# PCIE_CLK.net
KiCad netlist of a schematic drawn in Altium Designer
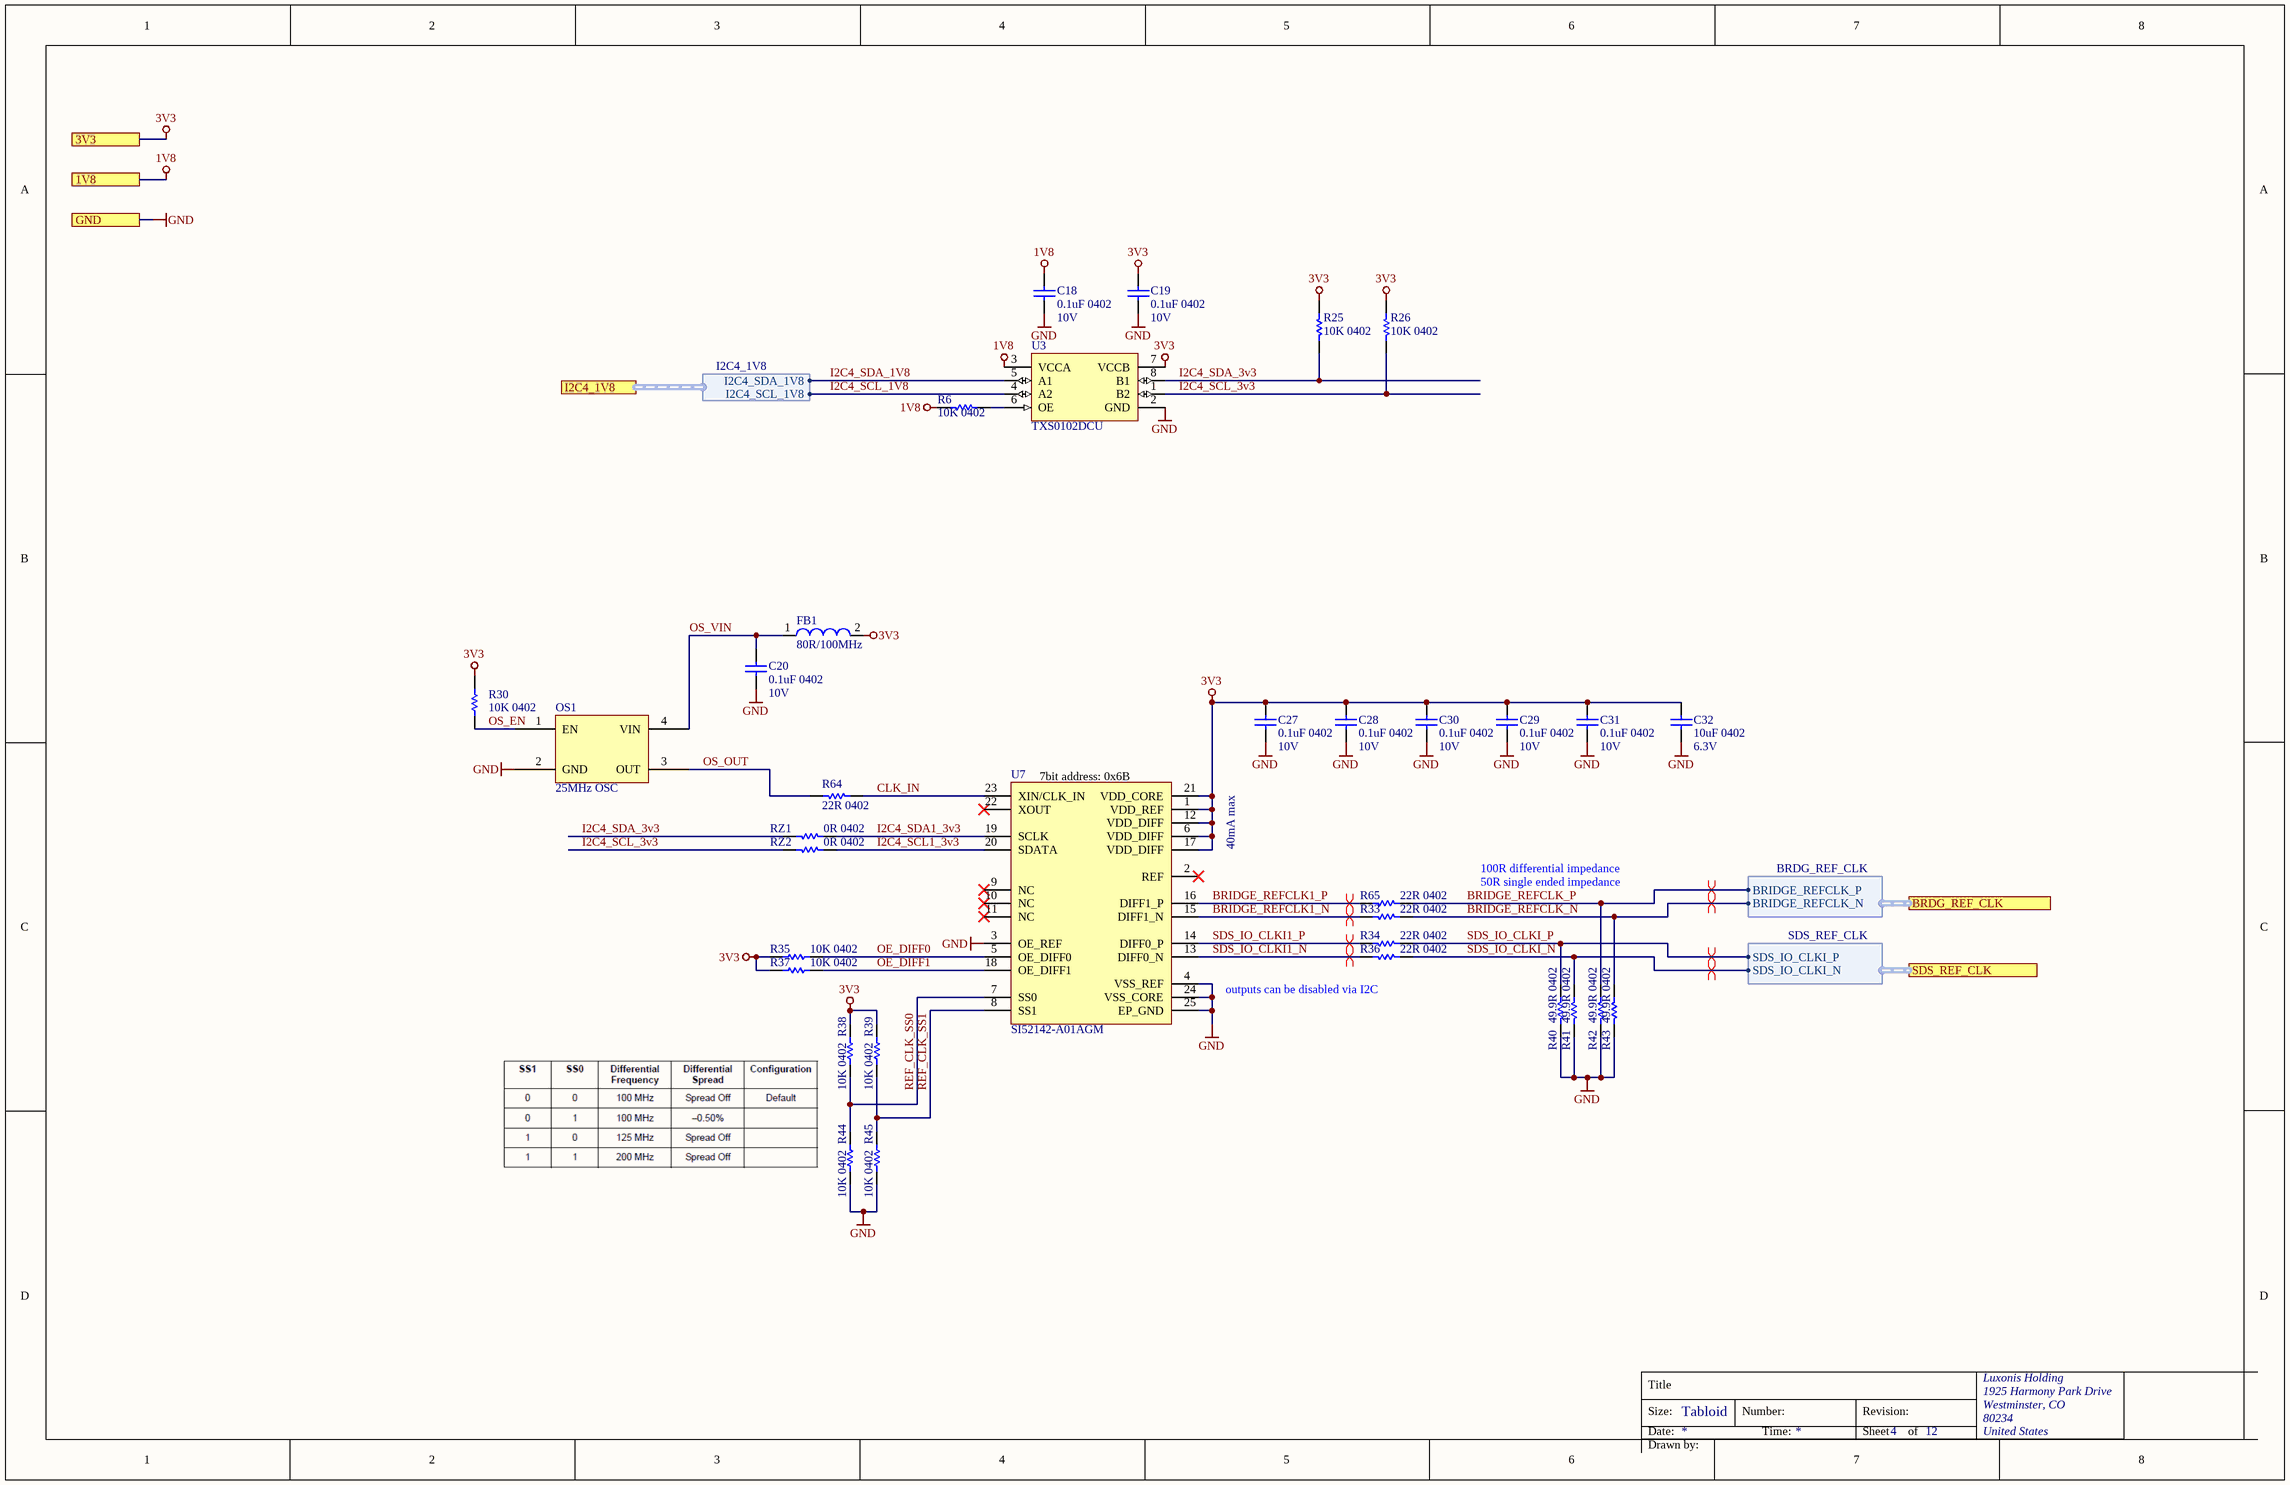
[diagram p0: PCIE_CLK.SchDoc]

(export (version "E")
  (design (tool "Eeschema 10.0.6"))
  (components
    (comp (ref "C18")
      (value "0.1uF 0402")
      (footprint "CAP_Altium_Vault_Generic:CAPC0402(1005)70_N")
      (description "CAP CER 0.1UF 10V X7R 0402 5%")
      (fields (field (name "TOLERANCE") "5%") (field (name "VOLTAGE RATING") "10V"))
      (libsource (lib "LuxonisMaster") (part "GRM155R71A104JA01D"))
    )
    (comp (ref "C19")
      (value "0.1uF 0402")
      (footprint "CAP_Altium_Vault_Generic:CAPC0402(1005)70_N")
      (description "CAP CER 0.1UF 10V X7R 0402 5%")
      (fields (field (name "TOLERANCE") "5%") (field (name "VOLTAGE RATING") "10V"))
      (libsource (lib "LuxonisMaster") (part "GRM155R71A104JA01D"))
    )
    (comp (ref "C20")
      (value "0.1uF 0402")
      (footprint "CAP_Altium_Vault_Generic:CAPC0402(1005)70_N")
      (description "CAP CER 0.1UF 10V X7R 0402 5%")
      (fields (field (name "TOLERANCE") "5%") (field (name "VOLTAGE RATING") "10V"))
      (libsource (lib "LuxonisMaster") (part "GRM155R71A104JA01D"))
    )
    (comp (ref "C27")
      (value "0.1uF 0402")
      (footprint "CAP_Altium_Vault_Generic:CAPC0402(1005)70_N")
      (description "CAP CER 0.1UF 10V X7R 0402 5%")
      (fields (field (name "TOLERANCE") "5%") (field (name "VOLTAGE RATING") "10V"))
      (libsource (lib "LuxonisMaster") (part "GRM155R71A104JA01D"))
    )
    (comp (ref "C28")
      (value "0.1uF 0402")
      (footprint "CAP_Altium_Vault_Generic:CAPC0402(1005)70_N")
      (description "CAP CER 0.1UF 10V X7R 0402 5%")
      (fields (field (name "TOLERANCE") "5%") (field (name "VOLTAGE RATING") "10V"))
      (libsource (lib "LuxonisMaster") (part "GRM155R71A104JA01D"))
    )
    (comp (ref "C29")
      (value "0.1uF 0402")
      (footprint "CAP_Altium_Vault_Generic:CAPC0402(1005)70_N")
      (description "CAP CER 0.1UF 10V X7R 0402 5%")
      (fields (field (name "TOLERANCE") "5%") (field (name "VOLTAGE RATING") "10V"))
      (libsource (lib "LuxonisMaster") (part "GRM155R71A104JA01D"))
    )
    (comp (ref "C30")
      (value "0.1uF 0402")
      (footprint "CAP_Altium_Vault_Generic:CAPC0402(1005)70_N")
      (description "CAP CER 0.1UF 10V X7R 0402 5%")
      (fields (field (name "TOLERANCE") "5%") (field (name "VOLTAGE RATING") "10V"))
      (libsource (lib "LuxonisMaster") (part "GRM155R71A104JA01D"))
    )
    (comp (ref "C31")
      (value "0.1uF 0402")
      (footprint "CAP_Altium_Vault_Generic:CAPC0402(1005)70_N")
      (description "CAP CER 0.1UF 10V X7R 0402 5%")
      (fields (field (name "TOLERANCE") "5%") (field (name "VOLTAGE RATING") "10V"))
      (libsource (lib "LuxonisMaster") (part "GRM155R71A104JA01D"))
    )
    (comp (ref "C32")
      (value "10uF 0402")
      (footprint "CAP_Altium_Vault_Generic:CAPC0402(1005)70_N")
      (description "CAP CER 10UF 6.3V X5R 0402 20%")
      (fields (field (name "TOLERANCE") "20%") (field (name "VOLTAGE RATING") "6.3V"))
      (libsource (lib "LuxonisMaster") (part "GRM155R60J106ME15D"))
    )
    (comp (ref "FB1")
      (value "80R/100MHz")
      (footprint "LuxonisMaster:BK1608HS800-T_N")
      (description "FERRITE BEAD 80 OHM 0603 1LN")
      (fields (field (name "TOLERANCE") "25%"))
      (libsource (lib "LuxonisMaster") (part "BK1608HS800-T"))
    )
    (comp (ref "OS1")
      (value "25MHz OSC")
      (footprint "BW2098POE:ASDMB-25.000MHZ-LC-T")
      (description "MEMS OSC XO 25.0000MHZ LVCMOS")
      (libsource (lib "BW2098POE") (part "ASDMB-25.000MHZ-LC-T"))
    )
    (comp (ref "R6")
      (value "10K 0402")
      (footprint "RES_Altium_Vault_Generic:RESC0402(1005)_N")
      (fields (field (name "TOLERANCE") "1%"))
      (libsource (lib "LuxonisMaster") (part "RC0402FR-1310KL"))
    )
    (comp (ref "R25")
      (value "10K 0402")
      (footprint "RES_Altium_Vault_Generic:RESC0402(1005)_N")
      (fields (field (name "TOLERANCE") "1%"))
      (libsource (lib "LuxonisMaster") (part "RC0402FR-1310KL"))
    )
    (comp (ref "R26")
      (value "10K 0402")
      (footprint "RES_Altium_Vault_Generic:RESC0402(1005)_N")
      (fields (field (name "TOLERANCE") "1%"))
      (libsource (lib "LuxonisMaster") (part "RC0402FR-1310KL"))
    )
    (comp (ref "R30")
      (value "10K 0402")
      (footprint "RES_Altium_Vault_Generic:RESC0402(1005)_N")
      (fields (field (name "TOLERANCE") "1%"))
      (libsource (lib "LuxonisMaster") (part "RC0402FR-1310KL"))
    )
    (comp (ref "R33")
      (value "22R 0402")
      (footprint "RES_Altium_Vault_Generic:RESC0402(1005)_L")
      (description "RES SMD 22 OHM 1% 1/16W 0402")
      (fields (field (name "TOLERANCE") "1%"))
      (libsource (lib "BW2098POE") (part "RC0402FR-0722RL"))
    )
    (comp (ref "R34")
      (value "22R 0402")
      (footprint "RES_Altium_Vault_Generic:RESC0402(1005)_L")
      (description "RES SMD 22 OHM 1% 1/16W 0402")
      (fields (field (name "TOLERANCE") "1%"))
      (libsource (lib "BW2098POE") (part "RC0402FR-0722RL"))
    )
    (comp (ref "R35")
      (value "10K 0402")
      (footprint "RES_Altium_Vault_Generic:RESC0402(1005)_N")
      (fields (field (name "TOLERANCE") "1%"))
      (libsource (lib "LuxonisMaster") (part "RC0402FR-1310KL"))
    )
    (comp (ref "R36")
      (value "22R 0402")
      (footprint "RES_Altium_Vault_Generic:RESC0402(1005)_L")
      (description "RES SMD 22 OHM 1% 1/16W 0402")
      (fields (field (name "TOLERANCE") "1%"))
      (libsource (lib "BW2098POE") (part "RC0402FR-0722RL"))
    )
    (comp (ref "R37")
      (value "10K 0402")
      (footprint "RES_Altium_Vault_Generic:RESC0402(1005)_N")
      (fields (field (name "TOLERANCE") "1%"))
      (libsource (lib "LuxonisMaster") (part "RC0402FR-1310KL"))
    )
    (comp (ref "R38")
      (value "10K 0402")
      (footprint "RES_Altium_Vault_Generic:RESC0402(1005)_N")
      (fields (field (name "TOLERANCE") "1%"))
      (libsource (lib "LuxonisMaster") (part "RC0402FR-1310KL"))
    )
    (comp (ref "R39")
      (value "10K 0402")
      (footprint "RES_Altium_Vault_Generic:RESC0402(1005)_N")
      (fields (field (name "TOLERANCE") "1%"))
      (libsource (lib "LuxonisMaster") (part "RC0402FR-1310KL"))
    )
    (comp (ref "R40")
      (value "49.9R 0402")
      (footprint "RES_Altium_Vault_Generic:RESC0402(1005)_L")
      (description "RES SMD 49.9 OHM 1% 1/16W 0402")
      (fields (field (name "TOLERANCE") "1%"))
      (libsource (lib "LuxonisMaster") (part "RC0402FR-0749R9L"))
    )
    (comp (ref "R41")
      (value "49.9R 0402")
      (footprint "RES_Altium_Vault_Generic:RESC0402(1005)_L")
      (description "RES SMD 49.9 OHM 1% 1/16W 0402")
      (fields (field (name "TOLERANCE") "1%"))
      (libsource (lib "LuxonisMaster") (part "RC0402FR-0749R9L"))
    )
    (comp (ref "R42")
      (value "49.9R 0402")
      (footprint "RES_Altium_Vault_Generic:RESC0402(1005)_L")
      (description "RES SMD 49.9 OHM 1% 1/16W 0402")
      (fields (field (name "TOLERANCE") "1%"))
      (libsource (lib "LuxonisMaster") (part "RC0402FR-0749R9L"))
    )
    (comp (ref "R43")
      (value "49.9R 0402")
      (footprint "RES_Altium_Vault_Generic:RESC0402(1005)_L")
      (description "RES SMD 49.9 OHM 1% 1/16W 0402")
      (fields (field (name "TOLERANCE") "1%"))
      (libsource (lib "LuxonisMaster") (part "RC0402FR-0749R9L"))
    )
    (comp (ref "R44")
      (value "10K 0402")
      (footprint "RES_Altium_Vault_Generic:RESC0402(1005)_N")
      (fields (field (name "TOLERANCE") "1%"))
      (libsource (lib "LuxonisMaster") (part "RC0402FR-1310KL"))
    )
    (comp (ref "R45")
      (value "10K 0402")
      (footprint "RES_Altium_Vault_Generic:RESC0402(1005)_N")
      (fields (field (name "TOLERANCE") "1%"))
      (libsource (lib "LuxonisMaster") (part "RC0402FR-1310KL"))
    )
    (comp (ref "R64")
      (value "22R 0402")
      (footprint "RES_Altium_Vault_Generic:RESC0402(1005)_N")
      (description "RES SMD 22 OHM 1% 1/16W 0402")
      (fields (field (name "TOLERANCE") "1%"))
      (libsource (lib "BW2098POE") (part "RC0402FR-0722RL"))
    )
    (comp (ref "R65")
      (value "22R 0402")
      (footprint "RES_Altium_Vault_Generic:RESC0402(1005)_L")
      (description "RES SMD 22 OHM 1% 1/16W 0402")
      (fields (field (name "TOLERANCE") "1%"))
      (libsource (lib "BW2098POE") (part "RC0402FR-0722RL"))
    )
    (comp (ref "RZ1")
      (value "0R 0402")
      (footprint "RES_Altium_Vault_Generic:RESC0402(1005)_N")
      (description "RES SMD 0 OHM JUMPER 1/16W 0402")
      (fields (field (name "TOLERANCE") "5%"))
      (libsource (lib "LuxonisMaster") (part "CRCW04020000Z0ED"))
    )
    (comp (ref "RZ2")
      (value "0R 0402")
      (footprint "RES_Altium_Vault_Generic:RESC0402(1005)_N")
      (description "RES SMD 0 OHM JUMPER 1/16W 0402")
      (fields (field (name "TOLERANCE") "5%"))
      (libsource (lib "LuxonisMaster") (part "CRCW04020000Z0ED"))
    )
    (comp (ref "U3")
      (value "TXS0102DCU")
      (footprint "BW2098POE:TXS0102DCUR")
      (description "TEXAS INSTRUMENTS - TXS0102DCUR - IC, TRANSLATOR, 2 BIT, BI, US-8")
      (libsource (lib "BW2098POE") (part "TXS0102DCUR"))
    )
    (comp (ref "U7")
      (value "SI52142-A01AGM")
      (footprint "BW2098POE:SI52142-A01AGM")
      (description "IC CLK GENERATOR 200MHZ 24QFN")
      (libsource (lib "BW2098POE") (part "SI52142-A01AGM"))
    )
  )
  (nets
    (net (code "4") (name "/BRIDGE_REFCLK1_N") (class "Default")
      (node (ref "R33") (pin "2") (pinfunction "2_2") (pintype "passive"))
      (node (ref "U7") (pin "15") (pinfunction "DIFF1_N_15") (pintype "passive"))
    )
    (net (code "5") (name "/BRIDGE_REFCLK1_P") (class "Default")
      (node (ref "R65") (pin "2") (pinfunction "2_2") (pintype "passive"))
      (node (ref "U7") (pin "16") (pinfunction "DIFF1_P_16") (pintype "passive"))
    )
    (net (code "6") (name "/BRIDGE_REFCLK_N") (class "Default")
      (node (ref "R33") (pin "1") (pinfunction "1_1") (pintype "passive"))
      (node (ref "R43") (pin "2") (pinfunction "2_2") (pintype "passive"))
    )
    (net (code "7") (name "/BRIDGE_REFCLK_P") (class "Default")
      (node (ref "R42") (pin "2") (pinfunction "2_2") (pintype "passive"))
      (node (ref "R65") (pin "1") (pinfunction "1_1") (pintype "passive"))
    )
    (net (code "8") (name "/CLK_IN") (class "Default")
      (node (ref "R64") (pin "1") (pinfunction "1_1") (pintype "passive"))
      (node (ref "U7") (pin "23") (pinfunction "XIN/CLK_IN_23") (pintype "passive"))
    )
    (net (code "9") (name "/I2C4_SCL1_3v3") (class "Default")
      (node (ref "RZ2") (pin "2") (pinfunction "2_2") (pintype "passive"))
      (node (ref "U7") (pin "20") (pinfunction "SDATA_20") (pintype "passive"))
    )
    (net (code "10") (name "/I2C4_SCL_1V8") (class "Default")
      (node (ref "U3") (pin "4") (pinfunction "A2_4") (pintype "bidirectional"))
    )
    (net (code "11") (name "/I2C4_SCL_3v3") (class "Default")
      (node (ref "R26") (pin "2") (pinfunction "2_2") (pintype "passive"))
      (node (ref "RZ2") (pin "1") (pinfunction "1_1") (pintype "passive"))
      (node (ref "U3") (pin "1") (pinfunction "B2_1") (pintype "bidirectional"))
    )
    (net (code "12") (name "/I2C4_SDA1_3v3") (class "Default")
      (node (ref "RZ1") (pin "2") (pinfunction "2_2") (pintype "passive"))
      (node (ref "U7") (pin "19") (pinfunction "SCLK_19") (pintype "passive"))
    )
    (net (code "13") (name "/I2C4_SDA_1V8") (class "Default")
      (node (ref "U3") (pin "5") (pinfunction "A1_5") (pintype "bidirectional"))
    )
    (net (code "14") (name "/I2C4_SDA_3v3") (class "Default")
      (node (ref "R25") (pin "2") (pinfunction "2_2") (pintype "passive"))
      (node (ref "RZ1") (pin "1") (pinfunction "1_1") (pintype "passive"))
      (node (ref "U3") (pin "8") (pinfunction "B1_8") (pintype "bidirectional"))
    )
    (net (code "15") (name "/OE_DIFF0") (class "Default")
      (node (ref "R35") (pin "2") (pinfunction "2_2") (pintype "passive"))
      (node (ref "U7") (pin "5") (pinfunction "OE_DIFF0_5") (pintype "passive"))
    )
    (net (code "16") (name "/OE_DIFF1") (class "Default")
      (node (ref "R37") (pin "2") (pinfunction "2_2") (pintype "passive"))
      (node (ref "U7") (pin "18") (pinfunction "OE_DIFF1_18") (pintype "passive"))
    )
    (net (code "17") (name "/OS_EN") (class "Default")
      (node (ref "OS1") (pin "1") (pinfunction "EN_1") (pintype "passive"))
      (node (ref "R30") (pin "1") (pinfunction "1_1") (pintype "passive"))
    )
    (net (code "18") (name "/OS_OUT") (class "Default")
      (node (ref "OS1") (pin "3") (pinfunction "OUT_3") (pintype "passive"))
      (node (ref "R64") (pin "2") (pinfunction "2_2") (pintype "passive"))
    )
    (net (code "19") (name "/OS_VIN") (class "Default")
      (node (ref "C20") (pin "1") (pinfunction "1_1") (pintype "passive"))
      (node (ref "FB1") (pin "1") (pinfunction "1_1") (pintype "passive"))
      (node (ref "OS1") (pin "4") (pinfunction "VIN_4") (pintype "passive"))
    )
    (net (code "20") (name "/REF_CLK_SS0") (class "Default")
      (node (ref "R38") (pin "2") (pinfunction "2_2") (pintype "passive"))
      (node (ref "R44") (pin "1") (pinfunction "1_1") (pintype "passive"))
      (node (ref "U7") (pin "7") (pinfunction "SS0_7") (pintype "passive"))
    )
    (net (code "21") (name "/REF_CLK_SS1") (class "Default")
      (node (ref "R39") (pin "2") (pinfunction "2_2") (pintype "passive"))
      (node (ref "R45") (pin "1") (pinfunction "1_1") (pintype "passive"))
      (node (ref "U7") (pin "8") (pinfunction "SS1_8") (pintype "passive"))
    )
    (net (code "22") (name "/SDS_IO_CLKI1_N") (class "Default")
      (node (ref "R36") (pin "2") (pinfunction "2_2") (pintype "passive"))
      (node (ref "U7") (pin "13") (pinfunction "DIFF0_N_13") (pintype "passive"))
    )
    (net (code "23") (name "/SDS_IO_CLKI1_P") (class "Default")
      (node (ref "R34") (pin "2") (pinfunction "2_2") (pintype "passive"))
      (node (ref "U7") (pin "14") (pinfunction "DIFF0_P_14") (pintype "passive"))
    )
    (net (code "24") (name "/SDS_IO_CLKI_N") (class "Default")
      (node (ref "R36") (pin "1") (pinfunction "1_1") (pintype "passive"))
      (node (ref "R41") (pin "2") (pinfunction "2_2") (pintype "passive"))
    )
    (net (code "25") (name "/SDS_IO_CLKI_P") (class "Default")
      (node (ref "R34") (pin "1") (pinfunction "1_1") (pintype "passive"))
      (node (ref "R40") (pin "1") (pinfunction "1_1") (pintype "passive"))
    )
    (net (code "29") (name "1V8") (class "Default")
      (node (ref "C18") (pin "2") (pinfunction "2_2") (pintype "passive"))
      (node (ref "R6") (pin "2") (pinfunction "2_2") (pintype "passive"))
      (node (ref "U3") (pin "3") (pinfunction "VCCA_3") (pintype "power_in"))
    )
    (net (code "30") (name "3V3") (class "Default")
      (node (ref "C19") (pin "2") (pinfunction "2_2") (pintype "passive"))
      (node (ref "C27") (pin "1") (pinfunction "1_1") (pintype "passive"))
      (node (ref "C28") (pin "1") (pinfunction "1_1") (pintype "passive"))
      (node (ref "C29") (pin "1") (pinfunction "1_1") (pintype "passive"))
      (node (ref "C30") (pin "1") (pinfunction "1_1") (pintype "passive"))
      (node (ref "C31") (pin "1") (pinfunction "1_1") (pintype "passive"))
      (node (ref "C32") (pin "2") (pinfunction "2_2") (pintype "passive"))
      (node (ref "FB1") (pin "2") (pinfunction "2_2") (pintype "passive"))
      (node (ref "R25") (pin "1") (pinfunction "1_1") (pintype "passive"))
      (node (ref "R26") (pin "1") (pinfunction "1_1") (pintype "passive"))
      (node (ref "R30") (pin "2") (pinfunction "2_2") (pintype "passive"))
      (node (ref "R35") (pin "1") (pinfunction "1_1") (pintype "passive"))
      (node (ref "R37") (pin "1") (pinfunction "1_1") (pintype "passive"))
      (node (ref "R38") (pin "1") (pinfunction "1_1") (pintype "passive"))
      (node (ref "R39") (pin "1") (pinfunction "1_1") (pintype "passive"))
      (node (ref "U3") (pin "7") (pinfunction "VCCB_7") (pintype "power_in"))
      (node (ref "U7") (pin "1") (pinfunction "VDD_REF_1") (pintype "passive"))
      (node (ref "U7") (pin "12") (pinfunction "VDD_DIFF_12") (pintype "passive"))
      (node (ref "U7") (pin "17") (pinfunction "VDD_DIFF_17") (pintype "passive"))
      (node (ref "U7") (pin "21") (pinfunction "VDD_CORE_21") (pintype "passive"))
      (node (ref "U7") (pin "6") (pinfunction "VDD_DIFF_6") (pintype "passive"))
    )
    (net (code "31") (name "GND") (class "Default")
      (node (ref "C18") (pin "1") (pinfunction "1_1") (pintype "passive"))
      (node (ref "C19") (pin "1") (pinfunction "1_1") (pintype "passive"))
      (node (ref "C20") (pin "2") (pinfunction "2_2") (pintype "passive"))
      (node (ref "C27") (pin "2") (pinfunction "2_2") (pintype "passive"))
      (node (ref "C28") (pin "2") (pinfunction "2_2") (pintype "passive"))
      (node (ref "C29") (pin "2") (pinfunction "2_2") (pintype "passive"))
      (node (ref "C30") (pin "2") (pinfunction "2_2") (pintype "passive"))
      (node (ref "C31") (pin "2") (pinfunction "2_2") (pintype "passive"))
      (node (ref "C32") (pin "1") (pinfunction "1_1") (pintype "passive"))
      (node (ref "OS1") (pin "2") (pinfunction "GND_2") (pintype "passive"))
      (node (ref "R40") (pin "2") (pinfunction "2_2") (pintype "passive"))
      (node (ref "R41") (pin "1") (pinfunction "1_1") (pintype "passive"))
      (node (ref "R42") (pin "1") (pinfunction "1_1") (pintype "passive"))
      (node (ref "R43") (pin "1") (pinfunction "1_1") (pintype "passive"))
      (node (ref "R44") (pin "2") (pinfunction "2_2") (pintype "passive"))
      (node (ref "R45") (pin "2") (pinfunction "2_2") (pintype "passive"))
      (node (ref "U3") (pin "2") (pinfunction "GND_2") (pintype "power_in"))
      (node (ref "U7") (pin "24") (pinfunction "VSS_CORE_24") (pintype "passive"))
      (node (ref "U7") (pin "25") (pinfunction "EP_GND_25") (pintype "passive"))
      (node (ref "U7") (pin "3") (pinfunction "OE_REF_3") (pintype "passive"))
      (node (ref "U7") (pin "4") (pinfunction "VSS_REF_4") (pintype "passive"))
    )
    (net (code "32") (name "Net-(U3-OE)") (class "Default")
      (node (ref "R6") (pin "1") (pinfunction "1_1") (pintype "passive"))
      (node (ref "U3") (pin "6") (pinfunction "OE_6") (pintype "input"))
    )
    (net (code "33") (name "unconnected-(U7-NC-Pad9)") (class "Default")
      (node (ref "U7") (pin "9") (pinfunction "NC_9") (pintype "passive+no_connect"))
    )
    (net (code "34") (name "unconnected-(U7-NC-Pad10)") (class "Default")
      (node (ref "U7") (pin "10") (pinfunction "NC_10") (pintype "passive+no_connect"))
    )
    (net (code "35") (name "unconnected-(U7-NC-Pad11)") (class "Default")
      (node (ref "U7") (pin "11") (pinfunction "NC_11") (pintype "passive+no_connect"))
    )
    (net (code "36") (name "unconnected-(U7-REF-Pad2)") (class "Default")
      (node (ref "U7") (pin "2") (pinfunction "REF_2") (pintype "passive+no_connect"))
    )
    (net (code "37") (name "unconnected-(U7-XOUT-Pad22)") (class "Default")
      (node (ref "U7") (pin "22") (pinfunction "XOUT_22") (pintype "passive+no_connect"))
    )
  )
)
